# r3eflow-v2-outdated.net
KiCad netlist of a schematic drawn in EAGLE
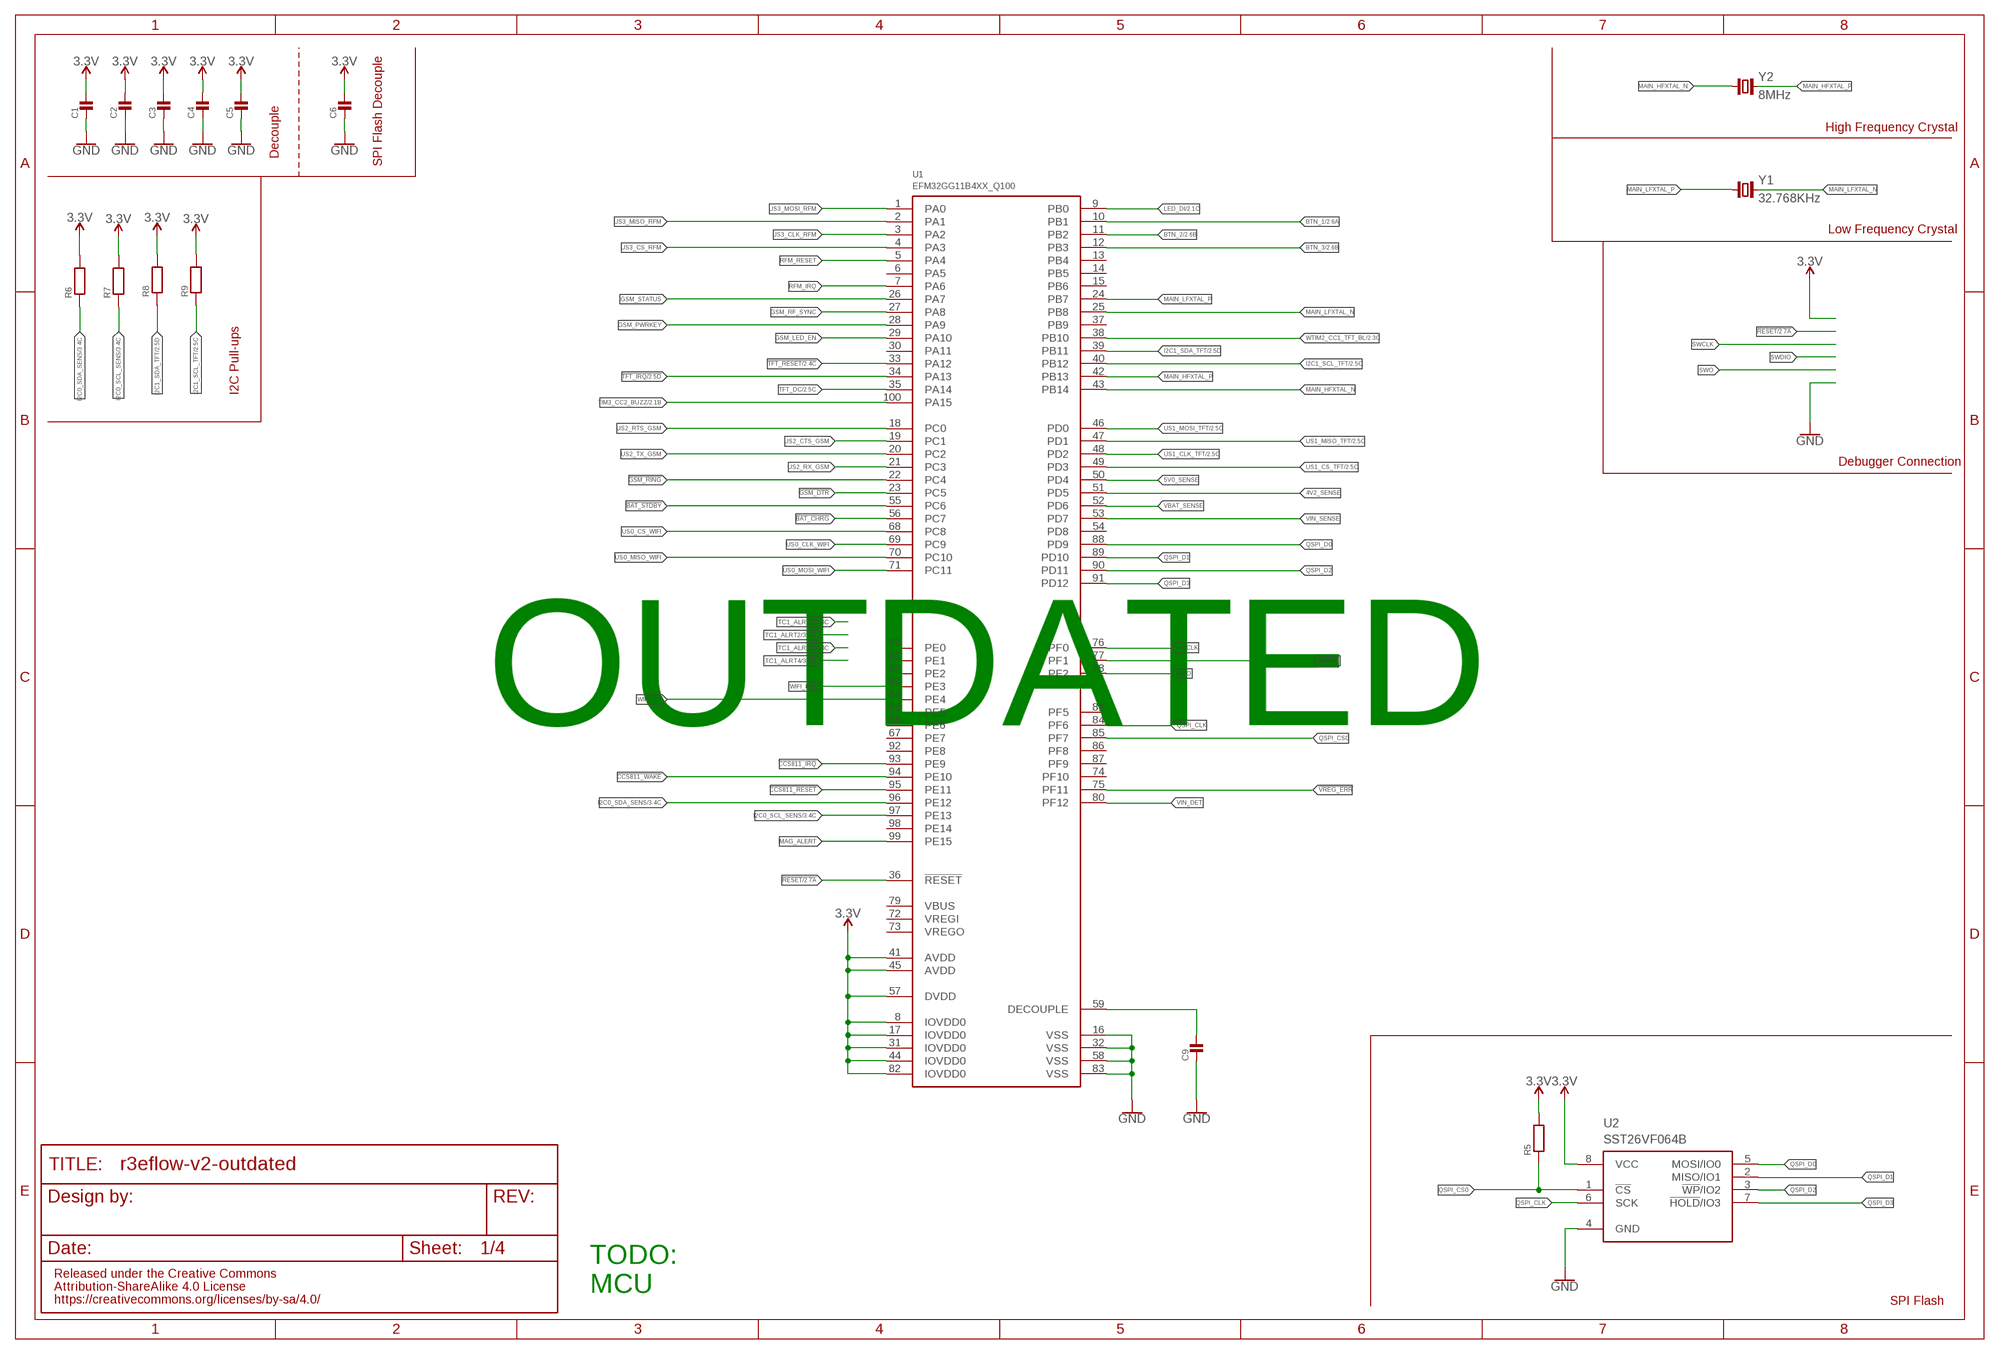
[diagram p0: schematic, sheet 1]
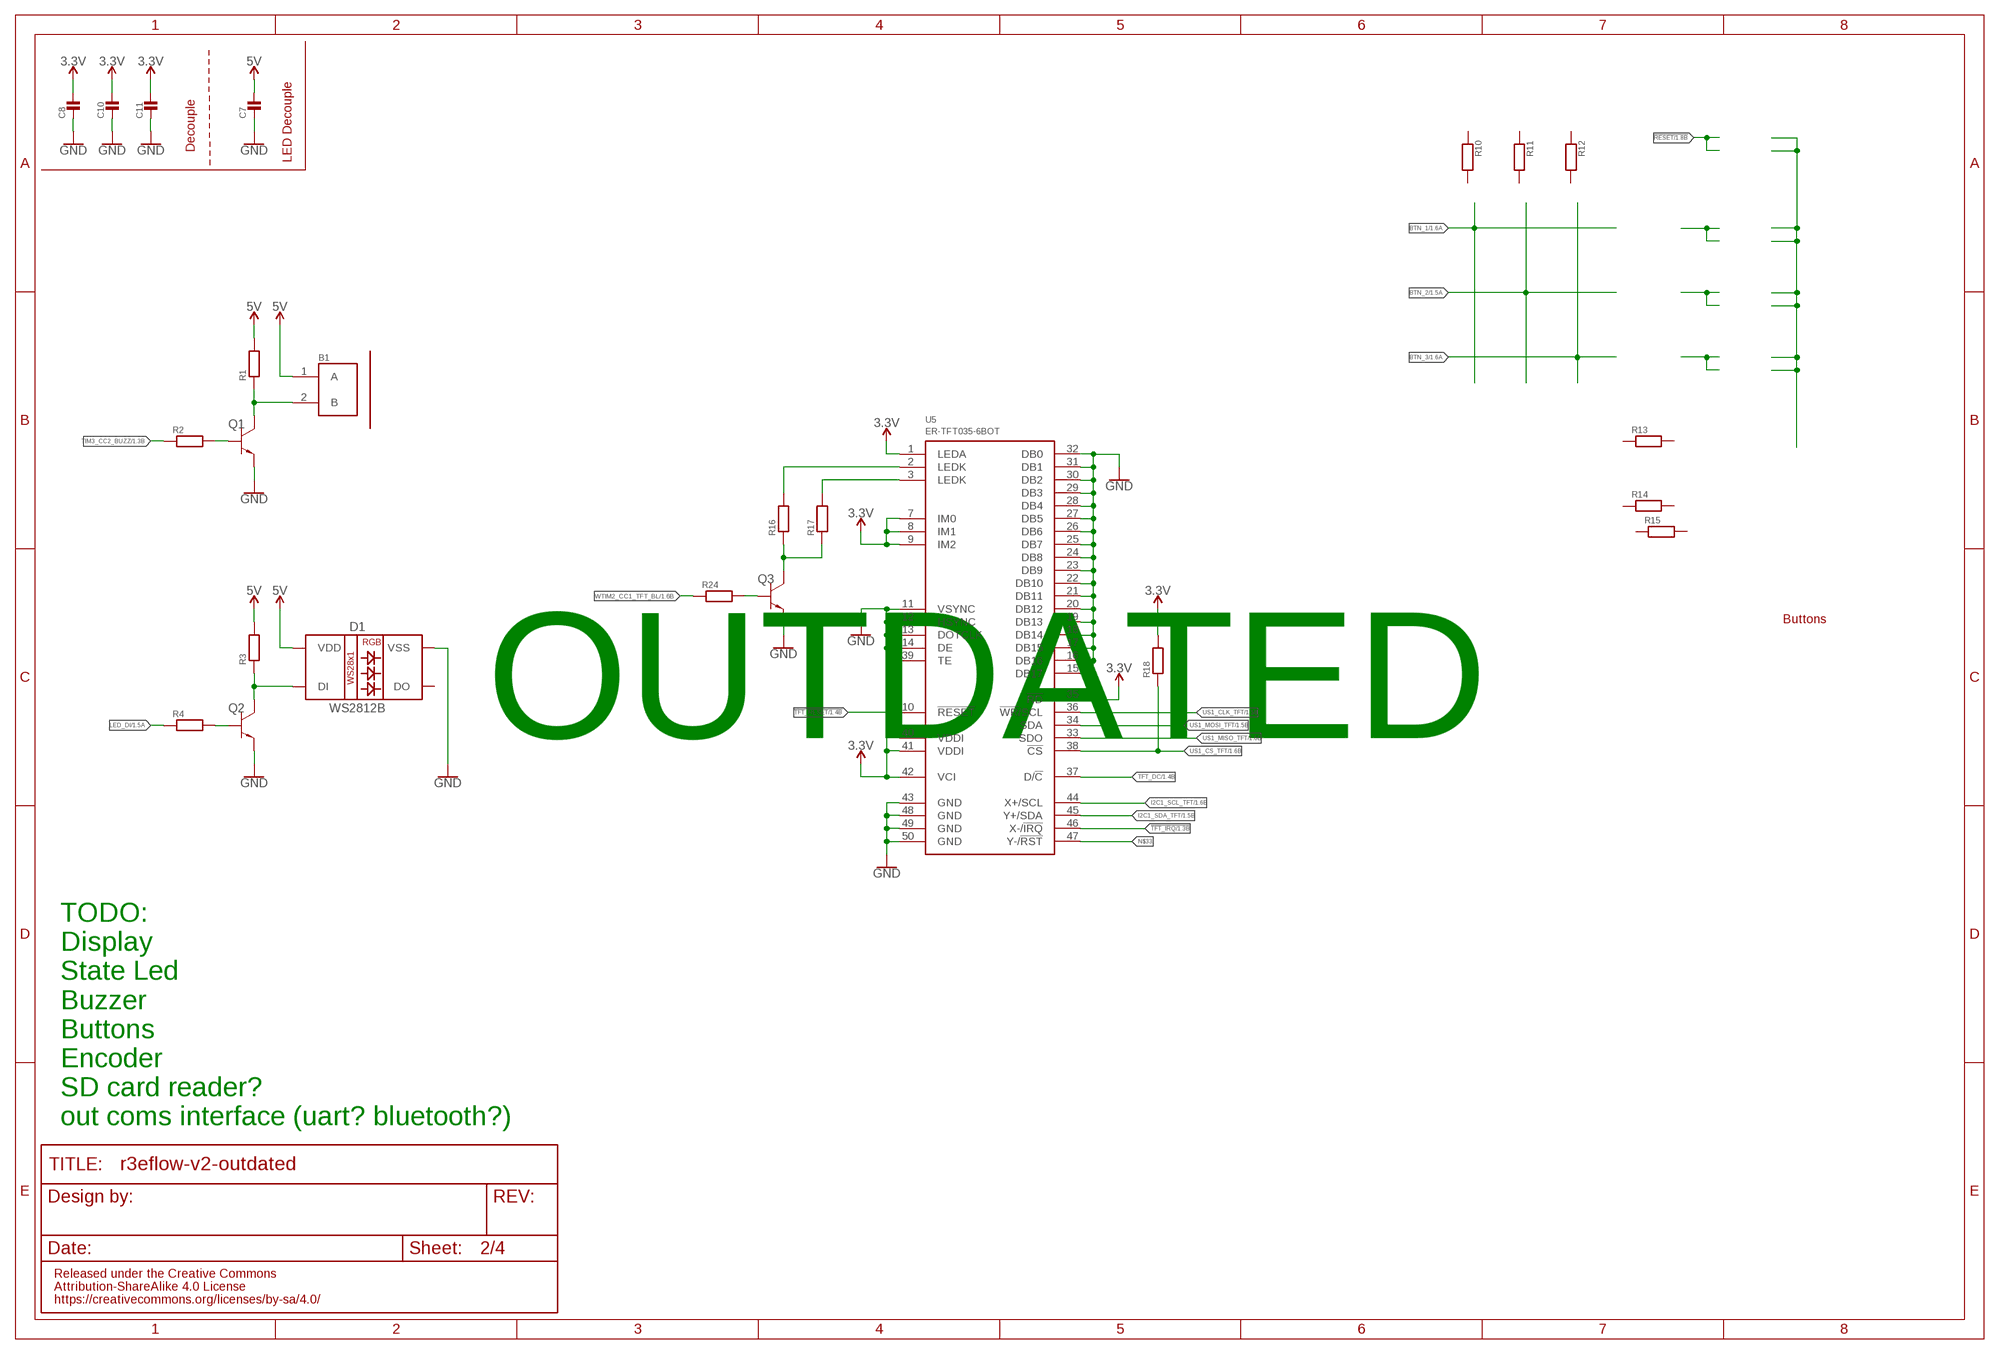
[diagram p1: schematic, sheet 2]
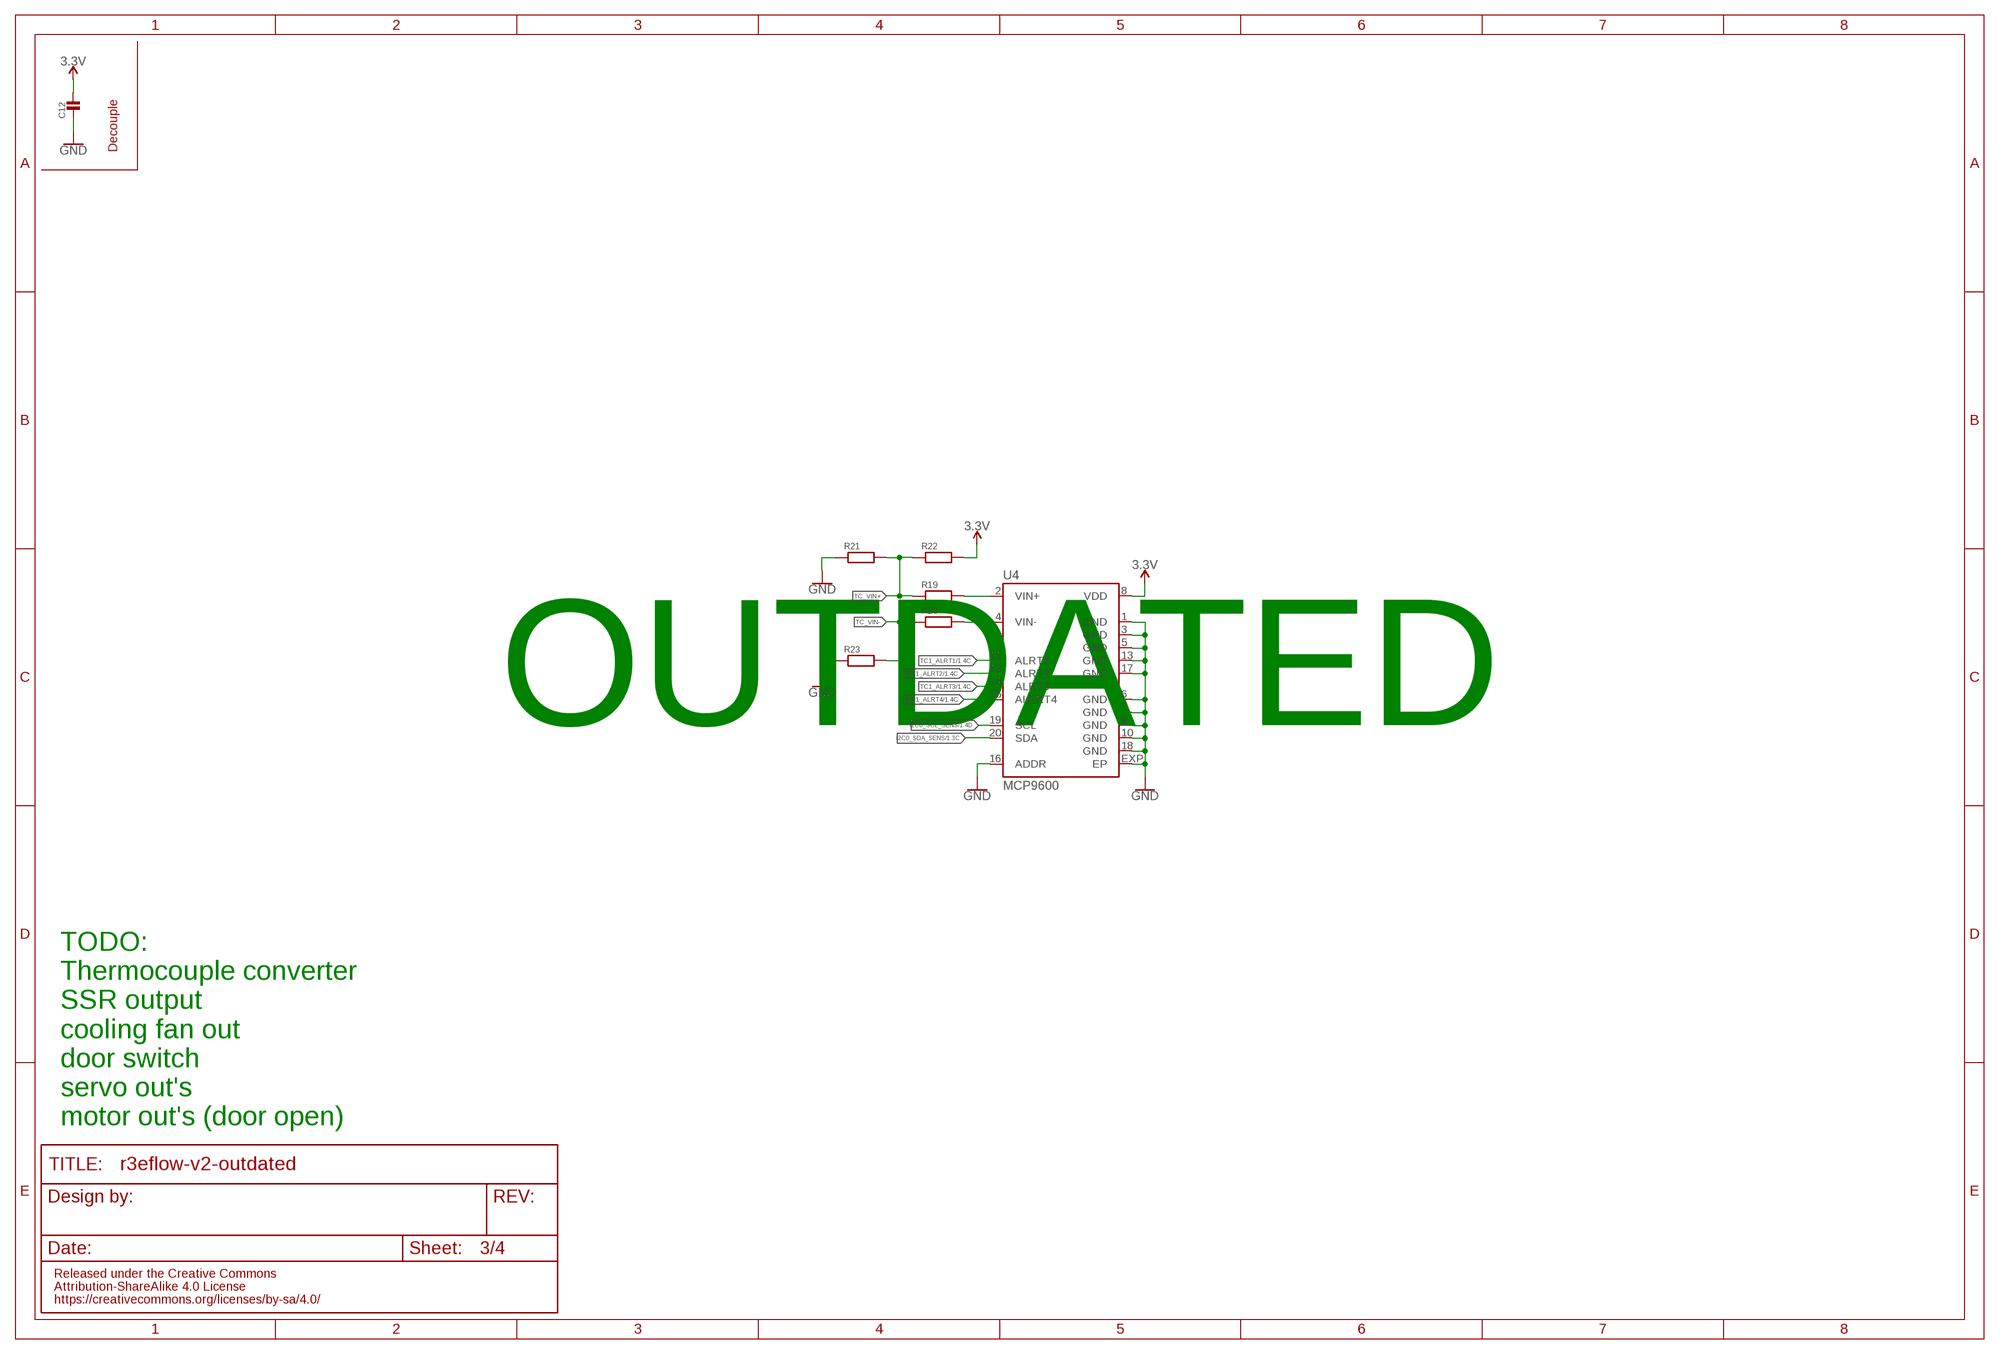
[diagram p2: schematic, sheet 3]
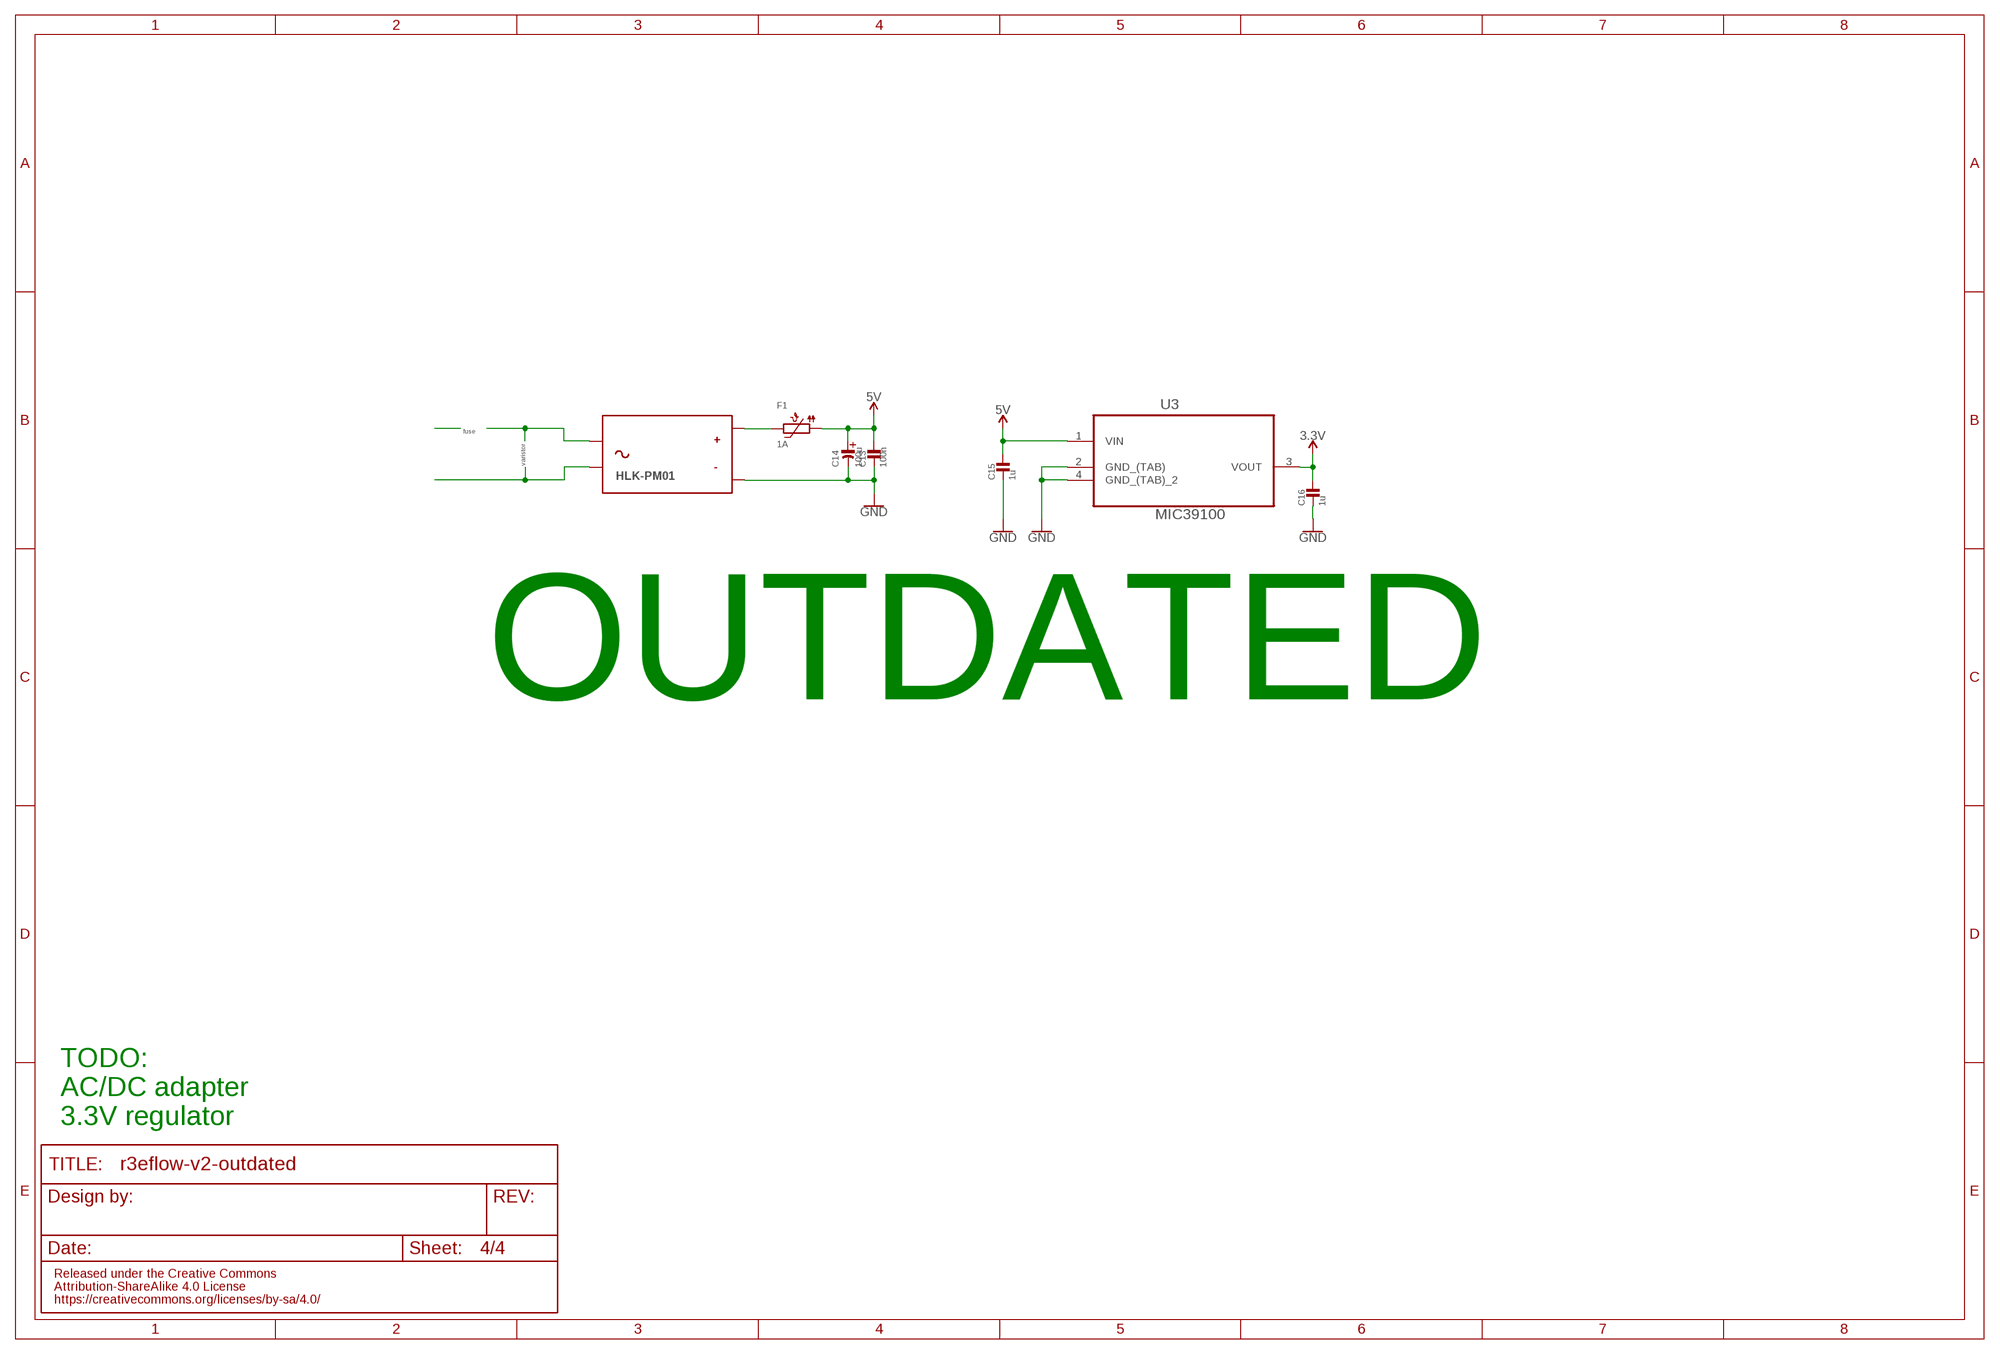
[diagram p3: schematic, sheet 4]

(export (version "E")
  (design (tool "Eeschema 10.0.6"))
  (components
    (comp (ref "C12")
      (value "MLCC0603")
      (footprint "eagle-import:0603_WAVE")
      (libsource (lib "eagle-import") (part "MLCC0603"))
    )
    (comp (ref "R19")
      (value "RESISTOR0603")
      (footprint "eagle-import:0603_WAVE")
      (libsource (lib "eagle-import") (part "RESISTOR0603"))
    )
    (comp (ref "R20")
      (value "RESISTOR0603")
      (footprint "eagle-import:0603_WAVE")
      (libsource (lib "eagle-import") (part "RESISTOR0603"))
    )
    (comp (ref "R21")
      (value "RESISTOR0603")
      (footprint "eagle-import:0603_WAVE")
      (libsource (lib "eagle-import") (part "RESISTOR0603"))
    )
    (comp (ref "R22")
      (value "RESISTOR0603")
      (footprint "eagle-import:0603_WAVE")
      (libsource (lib "eagle-import") (part "RESISTOR0603"))
    )
    (comp (ref "R23")
      (value "RESISTOR0603")
      (footprint "eagle-import:0603_WAVE")
      (libsource (lib "eagle-import") (part "RESISTOR0603"))
    )
    (comp (ref "U4")
      (value "MCP9600")
      (footprint "eagle-import:TQFN20-5X5")
      (libsource (lib "eagle-import") (part "MCP9600"))
    )
    (comp (ref "C13")
      (value "100n")
      (footprint "eagle-import:0603_WAVE")
      (libsource (lib "eagle-import") (part "MLCC0603"))
    )
    (comp (ref "C14")
      (value "100u")
      (footprint "eagle-import:10X10-EL")
      (libsource (lib "eagle-import") (part "CAPACITOR_EL10X10"))
    )
    (comp (ref "C15")
      (value "1u")
      (footprint "eagle-import:0603_WAVE")
      (libsource (lib "eagle-import") (part "MLCC0603"))
    )
    (comp (ref "C16")
      (value "1u")
      (footprint "eagle-import:0603_WAVE")
      (libsource (lib "eagle-import") (part "MLCC0603"))
    )
    (comp (ref "F1")
      (value "1A")
      (footprint "eagle-import:PTC1812")
      (libsource (lib "eagle-import") (part "PTC1812"))
    )
    (comp (ref "U$5")
      (value "HLK-PM01")
      (footprint "eagle-import:HLK-PM01")
      (libsource (lib "eagle-import") (part "HLK-PM01"))
    )
    (comp (ref "U3")
      (value "MIC39100")
      (footprint "eagle-import:SOT230P700X180-4N")
      (fields (field (name "MPN") "MCP1824ST-3302E/DB"))
      (libsource (lib "eagle-import") (part "MIC39100"))
    )
    (comp (ref "C1")
      (value "MLCC0603")
      (footprint "eagle-import:0603_WAVE")
      (libsource (lib "eagle-import") (part "MLCC0603"))
    )
    (comp (ref "C2")
      (value "MLCC0603")
      (footprint "eagle-import:0603_WAVE")
      (libsource (lib "eagle-import") (part "MLCC0603"))
    )
    (comp (ref "C3")
      (value "MLCC0603")
      (footprint "eagle-import:0603_WAVE")
      (libsource (lib "eagle-import") (part "MLCC0603"))
    )
    (comp (ref "C4")
      (value "MLCC0603")
      (footprint "eagle-import:0603_WAVE")
      (libsource (lib "eagle-import") (part "MLCC0603"))
    )
    (comp (ref "C5")
      (value "MLCC0603")
      (footprint "eagle-import:0603_WAVE")
      (libsource (lib "eagle-import") (part "MLCC0603"))
    )
    (comp (ref "C6")
      (value "MLCC0603")
      (footprint "eagle-import:0603_WAVE")
      (libsource (lib "eagle-import") (part "MLCC0603"))
    )
    (comp (ref "C9")
      (value "MLCC0603")
      (footprint "eagle-import:0603_WAVE")
      (libsource (lib "eagle-import") (part "MLCC0603"))
    )
    (comp (ref "R5")
      (value "RESISTOR0603")
      (footprint "eagle-import:0603_WAVE")
      (libsource (lib "eagle-import") (part "RESISTOR0603"))
    )
    (comp (ref "R6")
      (value "RESISTOR0603")
      (footprint "eagle-import:0603_WAVE")
      (libsource (lib "eagle-import") (part "RESISTOR0603"))
    )
    (comp (ref "R7")
      (value "RESISTOR0603")
      (footprint "eagle-import:0603_WAVE")
      (libsource (lib "eagle-import") (part "RESISTOR0603"))
    )
    (comp (ref "R8")
      (value "RESISTOR0603")
      (footprint "eagle-import:0603_WAVE")
      (libsource (lib "eagle-import") (part "RESISTOR0603"))
    )
    (comp (ref "R9")
      (value "RESISTOR0603")
      (footprint "eagle-import:0603_WAVE")
      (libsource (lib "eagle-import") (part "RESISTOR0603"))
    )
    (comp (ref "U1")
      (value "EFM32GG11B4XX_Q100")
      (footprint "eagle-import:QFP100")
      (libsource (lib "eagle-import") (part "EFM32GG11B4XX_Q100"))
    )
    (comp (ref "U2")
      (value "SST26VF064B")
      (footprint "eagle-import:WSOIC8")
      (libsource (lib "eagle-import") (part "SST26VF064B"))
    )
    (comp (ref "Y1")
      (value "32.768KHz")
      (footprint "eagle-import:CM200S")
      (libsource (lib "eagle-import") (part "CRYSTALCM200S"))
    )
    (comp (ref "Y2")
      (value "8MHz")
      (footprint "eagle-import:2-SMD-5X3")
      (libsource (lib "eagle-import") (part "CRYSTALNX5032GA"))
    )
    (comp (ref "B1")
      (value "PKLCS1212E2400-R1")
      (footprint "eagle-import:BUZZ_PIEZO_SMD")
      (libsource (lib "eagle-import") (part "PKLCS1212E2400-R1"))
    )
    (comp (ref "C7")
      (value "MLCC0603")
      (footprint "eagle-import:0603_WAVE")
      (libsource (lib "eagle-import") (part "MLCC0603"))
    )
    (comp (ref "C8")
      (value "MLCC0603")
      (footprint "eagle-import:0603_WAVE")
      (libsource (lib "eagle-import") (part "MLCC0603"))
    )
    (comp (ref "C10")
      (value "MLCC0603")
      (footprint "eagle-import:0603_WAVE")
      (libsource (lib "eagle-import") (part "MLCC0603"))
    )
    (comp (ref "C11")
      (value "MLCC0603")
      (footprint "eagle-import:0603_WAVE")
      (libsource (lib "eagle-import") (part "MLCC0603"))
    )
    (comp (ref "D1")
      (value "WS2812B")
      (footprint "eagle-import:WS2812B")
      (libsource (lib "eagle-import") (part "WS2812B"))
    )
    (comp (ref "Q1")
      (value "BC817-40")
      (footprint "eagle-import:SOT-23-3")
      (libsource (lib "eagle-import") (part "BC817-40"))
    )
    (comp (ref "Q2")
      (value "BC817-40")
      (footprint "eagle-import:SOT-23-3")
      (libsource (lib "eagle-import") (part "BC817-40"))
    )
    (comp (ref "Q3")
      (value "BC817-40")
      (footprint "eagle-import:SOT-23-3")
      (libsource (lib "eagle-import") (part "BC817-40"))
    )
    (comp (ref "R1")
      (value "RESISTOR0603")
      (footprint "eagle-import:0603_WAVE")
      (libsource (lib "eagle-import") (part "RESISTOR0603"))
    )
    (comp (ref "R2")
      (value "RESISTOR0603")
      (footprint "eagle-import:0603_WAVE")
      (libsource (lib "eagle-import") (part "RESISTOR0603"))
    )
    (comp (ref "R3")
      (value "RESISTOR0603")
      (footprint "eagle-import:0603_WAVE")
      (libsource (lib "eagle-import") (part "RESISTOR0603"))
    )
    (comp (ref "R4")
      (value "RESISTOR0603")
      (footprint "eagle-import:0603_WAVE")
      (libsource (lib "eagle-import") (part "RESISTOR0603"))
    )
    (comp (ref "R10")
      (value "RESISTOR0603")
      (footprint "eagle-import:0603_WAVE")
      (libsource (lib "eagle-import") (part "RESISTOR0603"))
    )
    (comp (ref "R11")
      (value "RESISTOR0603")
      (footprint "eagle-import:0603_WAVE")
      (libsource (lib "eagle-import") (part "RESISTOR0603"))
    )
    (comp (ref "R12")
      (value "RESISTOR0603")
      (footprint "eagle-import:0603_WAVE")
      (libsource (lib "eagle-import") (part "RESISTOR0603"))
    )
    (comp (ref "R13")
      (value "RESISTOR0603")
      (footprint "eagle-import:0603_WAVE")
      (libsource (lib "eagle-import") (part "RESISTOR0603"))
    )
    (comp (ref "R14")
      (value "RESISTOR0603")
      (footprint "eagle-import:0603_WAVE")
      (libsource (lib "eagle-import") (part "RESISTOR0603"))
    )
    (comp (ref "R15")
      (value "RESISTOR0603")
      (footprint "eagle-import:0603_WAVE")
      (libsource (lib "eagle-import") (part "RESISTOR0603"))
    )
    (comp (ref "R16")
      (value "RESISTOR0603")
      (footprint "eagle-import:0603_WAVE")
      (libsource (lib "eagle-import") (part "RESISTOR0603"))
    )
    (comp (ref "R17")
      (value "RESISTOR0603")
      (footprint "eagle-import:0603_WAVE")
      (libsource (lib "eagle-import") (part "RESISTOR0603"))
    )
    (comp (ref "R18")
      (value "RESISTOR0603")
      (footprint "eagle-import:0603_WAVE")
      (libsource (lib "eagle-import") (part "RESISTOR0603"))
    )
    (comp (ref "R24")
      (value "RESISTOR0603")
      (footprint "eagle-import:0603_WAVE")
      (libsource (lib "eagle-import") (part "RESISTOR0603"))
    )
    (comp (ref "U5")
      (value "ER-TFT035-6BOT")
      (footprint "eagle-import:ZIF50-TFT_BACK")
      (libsource (lib "eagle-import") (part "ER-TFT035-6BOT"))
    )
  )
  (nets
    (net (code "1") (name "3.3V") (class "Default")
      (node (ref "C1") (pin "P$1") (pinfunction "P$1_P$1") (pintype "bidirectional"))
      (node (ref "C10") (pin "P$1") (pinfunction "P$1_P$1") (pintype "bidirectional"))
      (node (ref "C11") (pin "P$1") (pinfunction "P$1_P$1") (pintype "bidirectional"))
      (node (ref "C12") (pin "P$1") (pinfunction "P$1_P$1") (pintype "bidirectional"))
      (node (ref "C16") (pin "P$1") (pinfunction "P$1_P$1") (pintype "bidirectional"))
      (node (ref "C2") (pin "P$1") (pinfunction "P$1_P$1") (pintype "bidirectional"))
      (node (ref "C3") (pin "P$1") (pinfunction "P$1_P$1") (pintype "bidirectional"))
      (node (ref "C4") (pin "P$1") (pinfunction "P$1_P$1") (pintype "bidirectional"))
      (node (ref "C5") (pin "P$1") (pinfunction "P$1_P$1") (pintype "bidirectional"))
      (node (ref "C6") (pin "P$1") (pinfunction "P$1_P$1") (pintype "bidirectional"))
      (node (ref "C8") (pin "P$1") (pinfunction "P$1_P$1") (pintype "bidirectional"))
      (node (ref "R18") (pin "P$2") (pinfunction "P$2_P$2") (pintype "bidirectional"))
      (node (ref "R22") (pin "P$2") (pinfunction "P$2_P$2") (pintype "bidirectional"))
      (node (ref "R5") (pin "P$2") (pinfunction "P$2_P$2") (pintype "bidirectional"))
      (node (ref "R6") (pin "P$2") (pinfunction "P$2_P$2") (pintype "bidirectional"))
      (node (ref "R7") (pin "P$2") (pinfunction "P$2_P$2") (pintype "bidirectional"))
      (node (ref "R8") (pin "P$2") (pinfunction "P$2_P$2") (pintype "bidirectional"))
      (node (ref "R9") (pin "P$2") (pinfunction "P$2_P$2") (pintype "bidirectional"))
      (node (ref "U1") (pin "17") (pinfunction "IOVDD0_17") (pintype "bidirectional"))
      (node (ref "U1") (pin "31") (pinfunction "IOVDD0_31") (pintype "bidirectional"))
      (node (ref "U1") (pin "41") (pinfunction "AVDD_41") (pintype "bidirectional"))
      (node (ref "U1") (pin "44") (pinfunction "IOVDD0_44") (pintype "bidirectional"))
      (node (ref "U1") (pin "45") (pinfunction "AVDD_45") (pintype "bidirectional"))
      (node (ref "U1") (pin "57") (pinfunction "DVDD_57") (pintype "bidirectional"))
      (node (ref "U1") (pin "8") (pinfunction "IOVDD0_8") (pintype "bidirectional"))
      (node (ref "U1") (pin "82") (pinfunction "IOVDD0_82") (pintype "bidirectional"))
      (node (ref "U2") (pin "8") (pinfunction "VCC_8") (pintype "power_in"))
      (node (ref "U3") (pin "3") (pinfunction "VOUT_3") (pintype "bidirectional"))
      (node (ref "U4") (pin "8") (pinfunction "VDD_8") (pintype "bidirectional"))
      (node (ref "U5") (pin "1") (pinfunction "LEDA_1") (pintype "bidirectional"))
      (node (ref "U5") (pin "35") (pinfunction "~{RD}_35") (pintype "bidirectional"))
      (node (ref "U5") (pin "40") (pinfunction "VDDI_40") (pintype "bidirectional"))
      (node (ref "U5") (pin "41") (pinfunction "VDDI_41") (pintype "bidirectional"))
      (node (ref "U5") (pin "42") (pinfunction "VCI_42") (pintype "bidirectional"))
      (node (ref "U5") (pin "7") (pinfunction "IM0_7") (pintype "bidirectional"))
      (node (ref "U5") (pin "8") (pinfunction "IM1_8") (pintype "bidirectional"))
      (node (ref "U5") (pin "9") (pinfunction "IM2_9") (pintype "bidirectional"))
    )
    (net (code "2") (name "4V2_SENSE") (class "Default")
      (node (ref "U1") (pin "51") (pinfunction "PD5_51") (pintype "bidirectional"))
    )
    (net (code "3") (name "5V") (class "Default")
      (node (ref "B1") (pin "1") (pinfunction "A_1") (pintype "bidirectional"))
      (node (ref "C13") (pin "P$1") (pinfunction "P$1_P$1") (pintype "bidirectional"))
      (node (ref "C14") (pin "AN") (pinfunction "AN_AN") (pintype "bidirectional"))
      (node (ref "C15") (pin "P$1") (pinfunction "P$1_P$1") (pintype "bidirectional"))
      (node (ref "C7") (pin "P$1") (pinfunction "P$1_P$1") (pintype "bidirectional"))
      (node (ref "D1") (pin "1") (pinfunction "VDD_1") (pintype "bidirectional"))
      (node (ref "F1") (pin "P$1") (pinfunction "1_P$1") (pintype "passive"))
      (node (ref "R1") (pin "P$2") (pinfunction "P$2_P$2") (pintype "bidirectional"))
      (node (ref "R3") (pin "P$2") (pinfunction "P$2_P$2") (pintype "bidirectional"))
      (node (ref "U3") (pin "1") (pinfunction "VIN_1") (pintype "input"))
    )
    (net (code "4") (name "5V0_SENSE") (class "Default")
      (node (ref "U1") (pin "50") (pinfunction "PD4_50") (pintype "bidirectional"))
    )
    (net (code "5") (name "BTN_1") (class "Default")
      (node (ref "U1") (pin "10") (pinfunction "PB1_10") (pintype "bidirectional"))
    )
    (net (code "6") (name "BTN_2") (class "Default")
      (node (ref "U1") (pin "11") (pinfunction "PB2_11") (pintype "bidirectional"))
    )
    (net (code "7") (name "BTN_3") (class "Default")
      (node (ref "U1") (pin "12") (pinfunction "PB3_12") (pintype "bidirectional"))
    )
    (net (code "8") (name "GND") (class "Default")
      (node (ref "C1") (pin "P$2") (pinfunction "P$2_P$2") (pintype "bidirectional"))
      (node (ref "C10") (pin "P$2") (pinfunction "P$2_P$2") (pintype "bidirectional"))
      (node (ref "C11") (pin "P$2") (pinfunction "P$2_P$2") (pintype "bidirectional"))
      (node (ref "C12") (pin "P$2") (pinfunction "P$2_P$2") (pintype "bidirectional"))
      (node (ref "C13") (pin "P$2") (pinfunction "P$2_P$2") (pintype "bidirectional"))
      (node (ref "C14") (pin "CAT") (pinfunction "CA_CAT") (pintype "bidirectional"))
      (node (ref "C15") (pin "P$2") (pinfunction "P$2_P$2") (pintype "bidirectional"))
      (node (ref "C16") (pin "P$2") (pinfunction "P$2_P$2") (pintype "bidirectional"))
      (node (ref "C2") (pin "P$2") (pinfunction "P$2_P$2") (pintype "bidirectional"))
      (node (ref "C3") (pin "P$2") (pinfunction "P$2_P$2") (pintype "bidirectional"))
      (node (ref "C4") (pin "P$2") (pinfunction "P$2_P$2") (pintype "bidirectional"))
      (node (ref "C5") (pin "P$2") (pinfunction "P$2_P$2") (pintype "bidirectional"))
      (node (ref "C6") (pin "P$2") (pinfunction "P$2_P$2") (pintype "bidirectional"))
      (node (ref "C7") (pin "P$2") (pinfunction "P$2_P$2") (pintype "bidirectional"))
      (node (ref "C8") (pin "P$2") (pinfunction "P$2_P$2") (pintype "bidirectional"))
      (node (ref "C9") (pin "P$2") (pinfunction "P$2_P$2") (pintype "bidirectional"))
      (node (ref "D1") (pin "3") (pinfunction "VSS_3") (pintype "bidirectional"))
      (node (ref "Q1") (pin "P$2") (pinfunction "EM2_P$2") (pintype "bidirectional"))
      (node (ref "Q2") (pin "P$2") (pinfunction "EM2_P$2") (pintype "bidirectional"))
      (node (ref "Q3") (pin "P$2") (pinfunction "EM2_P$2") (pintype "bidirectional"))
      (node (ref "R21") (pin "P$1") (pinfunction "P$1_P$1") (pintype "bidirectional"))
      (node (ref "R23") (pin "P$1") (pinfunction "P$1_P$1") (pintype "bidirectional"))
      (node (ref "U$5") (pin "-VO") (pinfunction "-VO_-VO") (pintype "bidirectional"))
      (node (ref "U1") (pin "16") (pinfunction "VSS_16") (pintype "bidirectional"))
      (node (ref "U1") (pin "32") (pinfunction "VSS_32") (pintype "bidirectional"))
      (node (ref "U1") (pin "58") (pinfunction "VSS_58") (pintype "bidirectional"))
      (node (ref "U1") (pin "83") (pinfunction "VSS_83") (pintype "bidirectional"))
      (node (ref "U2") (pin "4") (pinfunction "GND_4") (pintype "power_in"))
      (node (ref "U3") (pin "2") (pinfunction "GND_(TAB)_2") (pintype "bidirectional"))
      (node (ref "U3") (pin "4") (pinfunction "GND_(TAB)_2_4") (pintype "bidirectional"))
      (node (ref "U4") (pin "1") (pinfunction "GND_1") (pintype "bidirectional"))
      (node (ref "U4") (pin "10") (pinfunction "GND_10") (pintype "bidirectional"))
      (node (ref "U4") (pin "13") (pinfunction "GND_13") (pintype "bidirectional"))
      (node (ref "U4") (pin "16") (pinfunction "ADDR_16") (pintype "bidirectional"))
      (node (ref "U4") (pin "17") (pinfunction "GND_17") (pintype "bidirectional"))
      (node (ref "U4") (pin "18") (pinfunction "GND_18") (pintype "bidirectional"))
      (node (ref "U4") (pin "3") (pinfunction "GND_3") (pintype "bidirectional"))
      (node (ref "U4") (pin "5") (pinfunction "GND_5") (pintype "bidirectional"))
      (node (ref "U4") (pin "6") (pinfunction "GND_6") (pintype "bidirectional"))
      (node (ref "U4") (pin "7") (pinfunction "GND_7") (pintype "bidirectional"))
      (node (ref "U4") (pin "9") (pinfunction "GND_9") (pintype "bidirectional"))
      (node (ref "U4") (pin "EXP") (pinfunction "EP_EXP") (pintype "bidirectional"))
      (node (ref "U5") (pin "11") (pinfunction "VSYNC_11") (pintype "bidirectional"))
      (node (ref "U5") (pin "12") (pinfunction "HSYNC_12") (pintype "bidirectional"))
      (node (ref "U5") (pin "13") (pinfunction "DOTCLK_13") (pintype "bidirectional"))
      (node (ref "U5") (pin "14") (pinfunction "DE_14") (pintype "bidirectional"))
      (node (ref "U5") (pin "15") (pinfunction "DB17_15") (pintype "bidirectional"))
      (node (ref "U5") (pin "16") (pinfunction "DB16_16") (pintype "bidirectional"))
      (node (ref "U5") (pin "17") (pinfunction "DB15_17") (pintype "bidirectional"))
      (node (ref "U5") (pin "18") (pinfunction "DB14_18") (pintype "bidirectional"))
      (node (ref "U5") (pin "19") (pinfunction "DB13_19") (pintype "bidirectional"))
      (node (ref "U5") (pin "20") (pinfunction "DB12_20") (pintype "bidirectional"))
      (node (ref "U5") (pin "21") (pinfunction "DB11_21") (pintype "bidirectional"))
      (node (ref "U5") (pin "22") (pinfunction "DB10_22") (pintype "bidirectional"))
      (node (ref "U5") (pin "23") (pinfunction "DB9_23") (pintype "bidirectional"))
      (node (ref "U5") (pin "24") (pinfunction "DB8_24") (pintype "bidirectional"))
      (node (ref "U5") (pin "25") (pinfunction "DB7_25") (pintype "bidirectional"))
      (node (ref "U5") (pin "26") (pinfunction "DB6_26") (pintype "bidirectional"))
      (node (ref "U5") (pin "27") (pinfunction "DB5_27") (pintype "bidirectional"))
      (node (ref "U5") (pin "28") (pinfunction "DB4_28") (pintype "bidirectional"))
      (node (ref "U5") (pin "29") (pinfunction "DB3_29") (pintype "bidirectional"))
      (node (ref "U5") (pin "30") (pinfunction "DB2_30") (pintype "bidirectional"))
      (node (ref "U5") (pin "31") (pinfunction "DB1_31") (pintype "bidirectional"))
      (node (ref "U5") (pin "32") (pinfunction "DB0_32") (pintype "bidirectional"))
      (node (ref "U5") (pin "39") (pinfunction "TE_39") (pintype "bidirectional"))
      (node (ref "U5") (pin "43") (pinfunction "GND_43") (pintype "bidirectional"))
      (node (ref "U5") (pin "48") (pinfunction "GND_48") (pintype "bidirectional"))
      (node (ref "U5") (pin "49") (pinfunction "GND_49") (pintype "bidirectional"))
      (node (ref "U5") (pin "50") (pinfunction "GND_50") (pintype "bidirectional"))
    )
    (net (code "9") (name "GSM_LED_EN") (class "Default")
      (node (ref "U1") (pin "29") (pinfunction "PA10_29") (pintype "bidirectional"))
    )
    (net (code "10") (name "GSM_PWRKEY") (class "Default")
      (node (ref "U1") (pin "28") (pinfunction "PA9_28") (pintype "bidirectional"))
    )
    (net (code "11") (name "GSM_RF_SYNC") (class "Default")
      (node (ref "U1") (pin "27") (pinfunction "PA8_27") (pintype "bidirectional"))
    )
    (net (code "12") (name "GSM_STATUS") (class "Default")
      (node (ref "U1") (pin "26") (pinfunction "PA7_26") (pintype "bidirectional"))
    )
    (net (code "13") (name "I2C0_SCL_SENS") (class "Default")
      (node (ref "R7") (pin "P$1") (pinfunction "P$1_P$1") (pintype "bidirectional"))
      (node (ref "U1") (pin "97") (pinfunction "PE13_97") (pintype "bidirectional"))
      (node (ref "U4") (pin "19") (pinfunction "SCL_19") (pintype "bidirectional"))
    )
    (net (code "14") (name "I2C0_SDA_SENS") (class "Default")
      (node (ref "R6") (pin "P$1") (pinfunction "P$1_P$1") (pintype "bidirectional"))
      (node (ref "U1") (pin "96") (pinfunction "PE12_96") (pintype "bidirectional"))
      (node (ref "U4") (pin "20") (pinfunction "SDA_20") (pintype "bidirectional"))
    )
    (net (code "15") (name "I2C1_SCL_TFT") (class "Default")
      (node (ref "R9") (pin "P$1") (pinfunction "P$1_P$1") (pintype "bidirectional"))
      (node (ref "U1") (pin "40") (pinfunction "PB12_40") (pintype "bidirectional"))
      (node (ref "U5") (pin "44") (pinfunction "X+/SCL_44") (pintype "bidirectional"))
    )
    (net (code "16") (name "I2C1_SDA_TFT") (class "Default")
      (node (ref "R8") (pin "P$1") (pinfunction "P$1_P$1") (pintype "bidirectional"))
      (node (ref "U1") (pin "39") (pinfunction "PB11_39") (pintype "bidirectional"))
      (node (ref "U5") (pin "45") (pinfunction "Y+/SDA_45") (pintype "bidirectional"))
    )
    (net (code "17") (name "LED_DI") (class "Default")
      (node (ref "R4") (pin "P$1") (pinfunction "P$1_P$1") (pintype "bidirectional"))
      (node (ref "U1") (pin "9") (pinfunction "PB0_9") (pintype "bidirectional"))
    )
    (net (code "18") (name "MAG_ALERT") (class "Default")
      (node (ref "U1") (pin "99") (pinfunction "PE15_99") (pintype "bidirectional"))
    )
    (net (code "19") (name "MAIN_HFXTAL_N") (class "Default")
      (node (ref "U1") (pin "43") (pinfunction "PB14_43") (pintype "bidirectional"))
      (node (ref "Y2") (pin "1") (pinfunction "1_1") (pintype "passive"))
    )
    (net (code "20") (name "MAIN_HFXTAL_P") (class "Default")
      (node (ref "U1") (pin "42") (pinfunction "PB13_42") (pintype "bidirectional"))
      (node (ref "Y2") (pin "2") (pinfunction "2_2") (pintype "passive"))
    )
    (net (code "21") (name "MAIN_LFXTAL_N") (class "Default")
      (node (ref "U1") (pin "25") (pinfunction "PB8_25") (pintype "bidirectional"))
      (node (ref "Y1") (pin "4") (pinfunction "2_4") (pintype "passive"))
    )
    (net (code "22") (name "MAIN_LFXTAL_P") (class "Default")
      (node (ref "U1") (pin "24") (pinfunction "PB7_24") (pintype "bidirectional"))
      (node (ref "Y1") (pin "1") (pinfunction "1_1") (pintype "passive"))
    )
    (net (code "23") (name "N$33") (class "Default")
      (node (ref "U5") (pin "47") (pinfunction "Y-/~{RST}_47") (pintype "bidirectional"))
    )
    (net (code "24") (name "Net-(B1-B)") (class "Default")
      (node (ref "B1") (pin "2") (pinfunction "B_2") (pintype "bidirectional"))
      (node (ref "Q1") (pin "P$3") (pinfunction "C03_P$3") (pintype "bidirectional"))
      (node (ref "R1") (pin "P$1") (pinfunction "P$1_P$1") (pintype "bidirectional"))
    )
    (net (code "25") (name "Net-(D1-DI)") (class "Default")
      (node (ref "D1") (pin "4") (pinfunction "DI_4") (pintype "bidirectional"))
      (node (ref "Q2") (pin "P$3") (pinfunction "C03_P$3") (pintype "bidirectional"))
      (node (ref "R3") (pin "P$1") (pinfunction "P$1_P$1") (pintype "bidirectional"))
    )
    (net (code "26") (name "Net-(F1-2)") (class "Default")
      (node (ref "F1") (pin "P$2") (pinfunction "2_P$2") (pintype "passive"))
      (node (ref "U$5") (pin "+VO") (pinfunction "+VO_+VO") (pintype "bidirectional"))
    )
    (net (code "27") (name "Net-(Q1-BA1)") (class "Default")
      (node (ref "Q1") (pin "P$1") (pinfunction "BA1_P$1") (pintype "bidirectional"))
      (node (ref "R2") (pin "P$2") (pinfunction "P$2_P$2") (pintype "bidirectional"))
    )
    (net (code "28") (name "Net-(Q2-BA1)") (class "Default")
      (node (ref "Q2") (pin "P$1") (pinfunction "BA1_P$1") (pintype "bidirectional"))
      (node (ref "R4") (pin "P$2") (pinfunction "P$2_P$2") (pintype "bidirectional"))
    )
    (net (code "29") (name "Net-(Q3-BA1)") (class "Default")
      (node (ref "Q3") (pin "P$1") (pinfunction "BA1_P$1") (pintype "bidirectional"))
      (node (ref "R24") (pin "P$2") (pinfunction "P$2_P$2") (pintype "bidirectional"))
    )
    (net (code "30") (name "Net-(Q3-C03)") (class "Default")
      (node (ref "Q3") (pin "P$3") (pinfunction "C03_P$3") (pintype "bidirectional"))
      (node (ref "R16") (pin "P$1") (pinfunction "P$1_P$1") (pintype "bidirectional"))
      (node (ref "R17") (pin "P$1") (pinfunction "P$1_P$1") (pintype "bidirectional"))
    )
    (net (code "31") (name "Net-(R16-PadP$2)") (class "Default")
      (node (ref "R16") (pin "P$2") (pinfunction "P$2_P$2") (pintype "bidirectional"))
      (node (ref "U5") (pin "2") (pinfunction "LEDK_2") (pintype "bidirectional"))
    )
    (net (code "32") (name "Net-(R17-PadP$2)") (class "Default")
      (node (ref "R17") (pin "P$2") (pinfunction "P$2_P$2") (pintype "bidirectional"))
      (node (ref "U5") (pin "3") (pinfunction "LEDK_3") (pintype "bidirectional"))
    )
    (net (code "33") (name "Net-(U1-DECOUPLE)") (class "Default")
      (node (ref "C9") (pin "P$1") (pinfunction "P$1_P$1") (pintype "bidirectional"))
      (node (ref "U1") (pin "59") (pinfunction "DECOUPLE_59") (pintype "bidirectional"))
    )
    (net (code "34") (name "Net-(U4-VIN+)") (class "Default")
      (node (ref "R19") (pin "P$2") (pinfunction "P$2_P$2") (pintype "bidirectional"))
      (node (ref "U4") (pin "2") (pinfunction "VIN+_2") (pintype "bidirectional"))
    )
    (net (code "35") (name "Net-(U4-VIN-)") (class "Default")
      (node (ref "R20") (pin "P$2") (pinfunction "P$2_P$2") (pintype "bidirectional"))
      (node (ref "U4") (pin "4") (pinfunction "VIN-_4") (pintype "bidirectional"))
    )
    (net (code "36") (name "QSPI_CLK") (class "Default")
      (node (ref "U1") (pin "84") (pinfunction "PF6_84") (pintype "bidirectional"))
      (node (ref "U2") (pin "6") (pinfunction "SCK_6") (pintype "input"))
    )
    (net (code "37") (name "QSPI_CS0") (class "Default")
      (node (ref "R5") (pin "P$1") (pinfunction "P$1_P$1") (pintype "bidirectional"))
      (node (ref "U1") (pin "85") (pinfunction "PF7_85") (pintype "bidirectional"))
      (node (ref "U2") (pin "1") (pinfunction "~{CS}_1") (pintype "input"))
    )
    (net (code "38") (name "QSPI_D0") (class "Default")
      (node (ref "U1") (pin "88") (pinfunction "PD9_88") (pintype "bidirectional"))
      (node (ref "U2") (pin "5") (pinfunction "MOSI/IO0_5") (pintype "input"))
    )
    (net (code "39") (name "QSPI_D1") (class "Default")
      (node (ref "U1") (pin "89") (pinfunction "PD10_89") (pintype "bidirectional"))
      (node (ref "U2") (pin "2") (pinfunction "MISO/IO1_2") (pintype "output"))
    )
    (net (code "40") (name "QSPI_D2") (class "Default")
      (node (ref "U1") (pin "90") (pinfunction "PD11_90") (pintype "bidirectional"))
      (node (ref "U2") (pin "3") (pinfunction "~{WP}/IO2_3") (pintype "input"))
    )
    (net (code "41") (name "QSPI_D3") (class "Default")
      (node (ref "U1") (pin "91") (pinfunction "PD12_91") (pintype "bidirectional"))
      (node (ref "U2") (pin "7") (pinfunction "~{HOLD}/IO3_7") (pintype "input"))
    )
    (net (code "42") (name "RFM_IRQ") (class "Default")
      (node (ref "U1") (pin "7") (pinfunction "PA6_7") (pintype "bidirectional"))
    )
    (net (code "43") (name "RFM_RESET") (class "Default")
      (node (ref "U1") (pin "5") (pinfunction "PA4_5") (pintype "bidirectional"))
    )
    (net (code "44") (name "SWCLK") (class "Default")
      (node (ref "U1") (pin "76") (pinfunction "PF0_76") (pintype "bidirectional"))
    )
    (net (code "45") (name "SWDIO") (class "Default")
      (node (ref "U1") (pin "77") (pinfunction "PF1_77") (pintype "bidirectional"))
    )
    (net (code "46") (name "SWO") (class "Default")
      (node (ref "U1") (pin "78") (pinfunction "PF2_78") (pintype "bidirectional"))
    )
    (net (code "47") (name "TC1_ALRT1") (class "Default")
      (node (ref "U4") (pin "11") (pinfunction "ALRT1_11") (pintype "bidirectional"))
    )
    (net (code "48") (name "TC1_ALRT2") (class "Default")
      (node (ref "U4") (pin "12") (pinfunction "ALRT2_12") (pintype "bidirectional"))
    )
    (net (code "49") (name "TC1_ALRT3") (class "Default")
      (node (ref "U4") (pin "14") (pinfunction "ALRT3_14") (pintype "bidirectional"))
    )
    (net (code "50") (name "TC1_ALRT4") (class "Default")
      (node (ref "U4") (pin "15") (pinfunction "ALERT4_15") (pintype "bidirectional"))
    )
    (net (code "51") (name "TC_VIN+") (class "Default")
      (node (ref "R19") (pin "P$1") (pinfunction "P$1_P$1") (pintype "bidirectional"))
      (node (ref "R21") (pin "P$2") (pinfunction "P$2_P$2") (pintype "bidirectional"))
      (node (ref "R22") (pin "P$1") (pinfunction "P$1_P$1") (pintype "bidirectional"))
    )
    (net (code "52") (name "TC_VIN-") (class "Default")
      (node (ref "R20") (pin "P$1") (pinfunction "P$1_P$1") (pintype "bidirectional"))
      (node (ref "R23") (pin "P$2") (pinfunction "P$2_P$2") (pintype "bidirectional"))
    )
    (net (code "53") (name "TFT_DC") (class "Default")
      (node (ref "U1") (pin "35") (pinfunction "PA14_35") (pintype "bidirectional"))
      (node (ref "U5") (pin "37") (pinfunction "D/~{C}_37") (pintype "bidirectional"))
    )
    (net (code "54") (name "TIM3_CC2_BUZZ") (class "Default")
      (node (ref "R2") (pin "P$1") (pinfunction "P$1_P$1") (pintype "bidirectional"))
      (node (ref "U1") (pin "100") (pinfunction "PA15_100") (pintype "bidirectional"))
    )
    (net (code "55") (name "US0_CLK_WIFI") (class "Default")
      (node (ref "U1") (pin "69") (pinfunction "PC9_69") (pintype "bidirectional"))
    )
    (net (code "56") (name "US0_CS_WIFI") (class "Default")
      (node (ref "U1") (pin "68") (pinfunction "PC8_68") (pintype "bidirectional"))
    )
    (net (code "57") (name "US0_MISO_WIFI") (class "Default")
      (node (ref "U1") (pin "70") (pinfunction "PC10_70") (pintype "bidirectional"))
    )
    (net (code "58") (name "US0_MOSI_WIFI") (class "Default")
      (node (ref "U1") (pin "71") (pinfunction "PC11_71") (pintype "bidirectional"))
    )
    (net (code "59") (name "US1_CLK_TFT") (class "Default")
      (node (ref "U1") (pin "48") (pinfunction "PD2_48") (pintype "bidirectional"))
      (node (ref "U5") (pin "36") (pinfunction "~{WR}/SCL_36") (pintype "bidirectional"))
    )
    (net (code "60") (name "US1_CS_TFT") (class "Default")
      (node (ref "R18") (pin "P$1") (pinfunction "P$1_P$1") (pintype "bidirectional"))
      (node (ref "U1") (pin "49") (pinfunction "PD3_49") (pintype "bidirectional"))
      (node (ref "U5") (pin "38") (pinfunction "~{CS}_38") (pintype "bidirectional"))
    )
    (net (code "61") (name "US1_MISO_TFT") (class "Default")
      (node (ref "U1") (pin "47") (pinfunction "PD1_47") (pintype "bidirectional"))
      (node (ref "U5") (pin "33") (pinfunction "SDO_33") (pintype "bidirectional"))
    )
    (net (code "62") (name "US1_MOSI_TFT") (class "Default")
      (node (ref "U1") (pin "46") (pinfunction "PD0_46") (pintype "bidirectional"))
      (node (ref "U5") (pin "34") (pinfunction "SDA_34") (pintype "bidirectional"))
    )
    (net (code "63") (name "US2_CTS_GSM") (class "Default")
      (node (ref "U1") (pin "19") (pinfunction "PC1_19") (pintype "bidirectional"))
    )
    (net (code "64") (name "US2_RTS_GSM") (class "Default")
      (node (ref "U1") (pin "18") (pinfunction "PC0_18") (pintype "bidirectional"))
    )
    (net (code "65") (name "US2_RX_GSM") (class "Default")
      (node (ref "U1") (pin "21") (pinfunction "PC3_21") (pintype "bidirectional"))
    )
    (net (code "66") (name "US2_TX_GSM") (class "Default")
      (node (ref "U1") (pin "20") (pinfunction "PC2_20") (pintype "bidirectional"))
    )
    (net (code "67") (name "US3_CLK_RFM") (class "Default")
      (node (ref "U1") (pin "3") (pinfunction "PA2_3") (pintype "bidirectional"))
    )
    (net (code "68") (name "US3_CS_RFM") (class "Default")
      (node (ref "U1") (pin "4") (pinfunction "PA3_4") (pintype "bidirectional"))
    )
    (net (code "69") (name "US3_MISO_RFM") (class "Default")
      (node (ref "U1") (pin "2") (pinfunction "PA1_2") (pintype "bidirectional"))
    )
    (net (code "70") (name "US3_MOSI_RFM") (class "Default")
      (node (ref "U1") (pin "1") (pinfunction "PA0_1") (pintype "bidirectional"))
    )
    (net (code "71") (name "VBAT_SENSE") (class "Default")
      (node (ref "U1") (pin "52") (pinfunction "PD6_52") (pintype "bidirectional"))
    )
    (net (code "72") (name "VIN_DET") (class "Default")
      (node (ref "U1") (pin "80") (pinfunction "PF12_80") (pintype "bidirectional"))
    )
    (net (code "73") (name "VIN_SENSE") (class "Default")
      (node (ref "U1") (pin "53") (pinfunction "PD7_53") (pintype "bidirectional"))
    )
    (net (code "74") (name "WIFI_EN") (class "Default")
      (node (ref "U1") (pin "64") (pinfunction "PE4_64") (pintype "bidirectional"))
    )
    (net (code "75") (name "WIFI_IRQ") (class "Default")
      (node (ref "U1") (pin "63") (pinfunction "PE3_63") (pintype "bidirectional"))
    )
    (net (code "76") (name "WTIM2_CC1_TFT_BL") (class "Default")
      (node (ref "R24") (pin "P$1") (pinfunction "P$1_P$1") (pintype "bidirectional"))
      (node (ref "U1") (pin "38") (pinfunction "PB10_38") (pintype "bidirectional"))
    )
    (net (code "77") (name "unconnected-(D1-DO-Pad2)") (class "Default")
      (node (ref "D1") (pin "2") (pinfunction "DO_2") (pintype "bidirectional"))
    )
    (net (code "78") (name "unconnected-(R10-PadP$1)") (class "Default")
      (node (ref "R10") (pin "P$1") (pinfunction "P$1_P$1") (pintype "bidirectional"))
    )
    (net (code "79") (name "unconnected-(R10-PadP$2)") (class "Default")
      (node (ref "R10") (pin "P$2") (pinfunction "P$2_P$2") (pintype "bidirectional"))
    )
    (net (code "80") (name "unconnected-(R11-PadP$1)") (class "Default")
      (node (ref "R11") (pin "P$1") (pinfunction "P$1_P$1") (pintype "bidirectional"))
    )
    (net (code "81") (name "unconnected-(R11-PadP$2)") (class "Default")
      (node (ref "R11") (pin "P$2") (pinfunction "P$2_P$2") (pintype "bidirectional"))
    )
    (net (code "82") (name "unconnected-(R12-PadP$1)") (class "Default")
      (node (ref "R12") (pin "P$1") (pinfunction "P$1_P$1") (pintype "bidirectional"))
    )
    (net (code "83") (name "unconnected-(R12-PadP$2)") (class "Default")
      (node (ref "R12") (pin "P$2") (pinfunction "P$2_P$2") (pintype "bidirectional"))
    )
    (net (code "84") (name "unconnected-(R13-PadP$1)") (class "Default")
      (node (ref "R13") (pin "P$1") (pinfunction "P$1_P$1") (pintype "bidirectional"))
    )
    (net (code "85") (name "unconnected-(R13-PadP$2)") (class "Default")
      (node (ref "R13") (pin "P$2") (pinfunction "P$2_P$2") (pintype "bidirectional"))
    )
    (net (code "86") (name "unconnected-(R14-PadP$1)") (class "Default")
      (node (ref "R14") (pin "P$1") (pinfunction "P$1_P$1") (pintype "bidirectional"))
    )
    (net (code "87") (name "unconnected-(R14-PadP$2)") (class "Default")
      (node (ref "R14") (pin "P$2") (pinfunction "P$2_P$2") (pintype "bidirectional"))
    )
    (net (code "88") (name "unconnected-(R15-PadP$1)") (class "Default")
      (node (ref "R15") (pin "P$1") (pinfunction "P$1_P$1") (pintype "bidirectional"))
    )
    (net (code "89") (name "unconnected-(R15-PadP$2)") (class "Default")
      (node (ref "R15") (pin "P$2") (pinfunction "P$2_P$2") (pintype "bidirectional"))
    )
    (net (code "90") (name "unconnected-(U$5-PadAC1)") (class "Default")
      (node (ref "U$5") (pin "AC1") (pinfunction "AC1_AC1") (pintype "bidirectional"))
    )
    (net (code "91") (name "unconnected-(U$5-PadAC2)") (class "Default")
      (node (ref "U$5") (pin "AC2") (pinfunction "AC2_AC2") (pintype "bidirectional"))
    )
    (net (code "92") (name "unconnected-(U1-PA5-Pad6)") (class "Default")
      (node (ref "U1") (pin "6") (pinfunction "PA5_6") (pintype "bidirectional"))
    )
    (net (code "93") (name "unconnected-(U1-PA11-Pad30)") (class "Default")
      (node (ref "U1") (pin "30") (pinfunction "PA11_30") (pintype "bidirectional"))
    )
    (net (code "94") (name "unconnected-(U1-PB4-Pad13)") (class "Default")
      (node (ref "U1") (pin "13") (pinfunction "PB4_13") (pintype "bidirectional"))
    )
    (net (code "95") (name "unconnected-(U1-PB5-Pad14)") (class "Default")
      (node (ref "U1") (pin "14") (pinfunction "PB5_14") (pintype "bidirectional"))
    )
    (net (code "96") (name "unconnected-(U1-PB6-Pad15)") (class "Default")
      (node (ref "U1") (pin "15") (pinfunction "PB6_15") (pintype "bidirectional"))
    )
    (net (code "97") (name "unconnected-(U1-PB9-Pad37)") (class "Default")
      (node (ref "U1") (pin "37") (pinfunction "PB9_37") (pintype "bidirectional"))
    )
    (net (code "98") (name "unconnected-(U1-PD8-Pad54)") (class "Default")
      (node (ref "U1") (pin "54") (pinfunction "PD8_54") (pintype "bidirectional"))
    )
    (net (code "99") (name "unconnected-(U1-PE0-Pad60)") (class "Default")
      (node (ref "U1") (pin "60") (pinfunction "PE0_60") (pintype "bidirectional"))
    )
    (net (code "100") (name "unconnected-(U1-PE1-Pad61)") (class "Default")
      (node (ref "U1") (pin "61") (pinfunction "PE1_61") (pintype "bidirectional"))
    )
    (net (code "101") (name "unconnected-(U1-PE2-Pad62)") (class "Default")
      (node (ref "U1") (pin "62") (pinfunction "PE2_62") (pintype "bidirectional"))
    )
    (net (code "102") (name "unconnected-(U1-PE5-Pad65)") (class "Default")
      (node (ref "U1") (pin "65") (pinfunction "PE5_65") (pintype "bidirectional"))
    )
    (net (code "103") (name "unconnected-(U1-PE6-Pad66)") (class "Default")
      (node (ref "U1") (pin "66") (pinfunction "PE6_66") (pintype "bidirectional"))
    )
    (net (code "104") (name "unconnected-(U1-PE7-Pad67)") (class "Default")
      (node (ref "U1") (pin "67") (pinfunction "PE7_67") (pintype "bidirectional"))
    )
    (net (code "105") (name "unconnected-(U1-PE8-Pad92)") (class "Default")
      (node (ref "U1") (pin "92") (pinfunction "PE8_92") (pintype "bidirectional"))
    )
    (net (code "106") (name "unconnected-(U1-PE14-Pad98)") (class "Default")
      (node (ref "U1") (pin "98") (pinfunction "PE14_98") (pintype "bidirectional"))
    )
    (net (code "107") (name "unconnected-(U1-PF5-Pad81)") (class "Default")
      (node (ref "U1") (pin "81") (pinfunction "PF5_81") (pintype "bidirectional"))
    )
    (net (code "108") (name "unconnected-(U1-PF8-Pad86)") (class "Default")
      (node (ref "U1") (pin "86") (pinfunction "PF8_86") (pintype "bidirectional"))
    )
    (net (code "109") (name "unconnected-(U1-PF9-Pad87)") (class "Default")
      (node (ref "U1") (pin "87") (pinfunction "PF9_87") (pintype "bidirectional"))
    )
    (net (code "110") (name "unconnected-(U1-PF10-Pad74)") (class "Default")
      (node (ref "U1") (pin "74") (pinfunction "PF10_74") (pintype "bidirectional"))
    )
    (net (code "111") (name "unconnected-(U1-VBUS-Pad79)") (class "Default")
      (node (ref "U1") (pin "79") (pinfunction "VBUS_79") (pintype "bidirectional"))
    )
    (net (code "112") (name "unconnected-(U1-VREGI-Pad72)") (class "Default")
      (node (ref "U1") (pin "72") (pinfunction "VREGI_72") (pintype "bidirectional"))
    )
    (net (code "113") (name "unconnected-(U1-VREGO-Pad73)") (class "Default")
      (node (ref "U1") (pin "73") (pinfunction "VREGO_73") (pintype "bidirectional"))
    )
    (net (code "114") (name "~{BAT_CHRG}") (class "Default")
      (node (ref "U1") (pin "56") (pinfunction "PC7_56") (pintype "bidirectional"))
    )
    (net (code "115") (name "~{BAT_STDBY}") (class "Default")
      (node (ref "U1") (pin "55") (pinfunction "PC6_55") (pintype "bidirectional"))
    )
    (net (code "116") (name "~{CCS811_IRQ}") (class "Default")
      (node (ref "U1") (pin "93") (pinfunction "PE9_93") (pintype "bidirectional"))
    )
    (net (code "117") (name "~{CCS811_RESET}") (class "Default")
      (node (ref "U1") (pin "95") (pinfunction "PE11_95") (pintype "bidirectional"))
    )
    (net (code "118") (name "~{CCS811_WAKE}") (class "Default")
      (node (ref "U1") (pin "94") (pinfunction "PE10_94") (pintype "bidirectional"))
    )
    (net (code "119") (name "~{GSM_DTR}") (class "Default")
      (node (ref "U1") (pin "23") (pinfunction "PC5_23") (pintype "bidirectional"))
    )
    (net (code "120") (name "~{GSM_RING}") (class "Default")
      (node (ref "U1") (pin "22") (pinfunction "PC4_22") (pintype "bidirectional"))
    )
    (net (code "121") (name "~{RESET}") (class "Default")
      (node (ref "U1") (pin "36") (pinfunction "~{RESET}_36") (pintype "bidirectional"))
    )
    (net (code "122") (name "~{TFT_IRQ}") (class "Default")
      (node (ref "U1") (pin "34") (pinfunction "PA13_34") (pintype "bidirectional"))
      (node (ref "U5") (pin "46") (pinfunction "X-/~{IRQ}_46") (pintype "bidirectional"))
    )
    (net (code "123") (name "~{TFT_RESET}") (class "Default")
      (node (ref "U1") (pin "33") (pinfunction "PA12_33") (pintype "bidirectional"))
      (node (ref "U5") (pin "10") (pinfunction "~{RESET}_10") (pintype "bidirectional"))
    )
    (net (code "124") (name "~{VREG_ERR}") (class "Default")
      (node (ref "U1") (pin "75") (pinfunction "PF11_75") (pintype "bidirectional"))
    )
  )
)
